# Bank0_I_O.net
KiCad netlist of a schematic drawn in Altium Designer
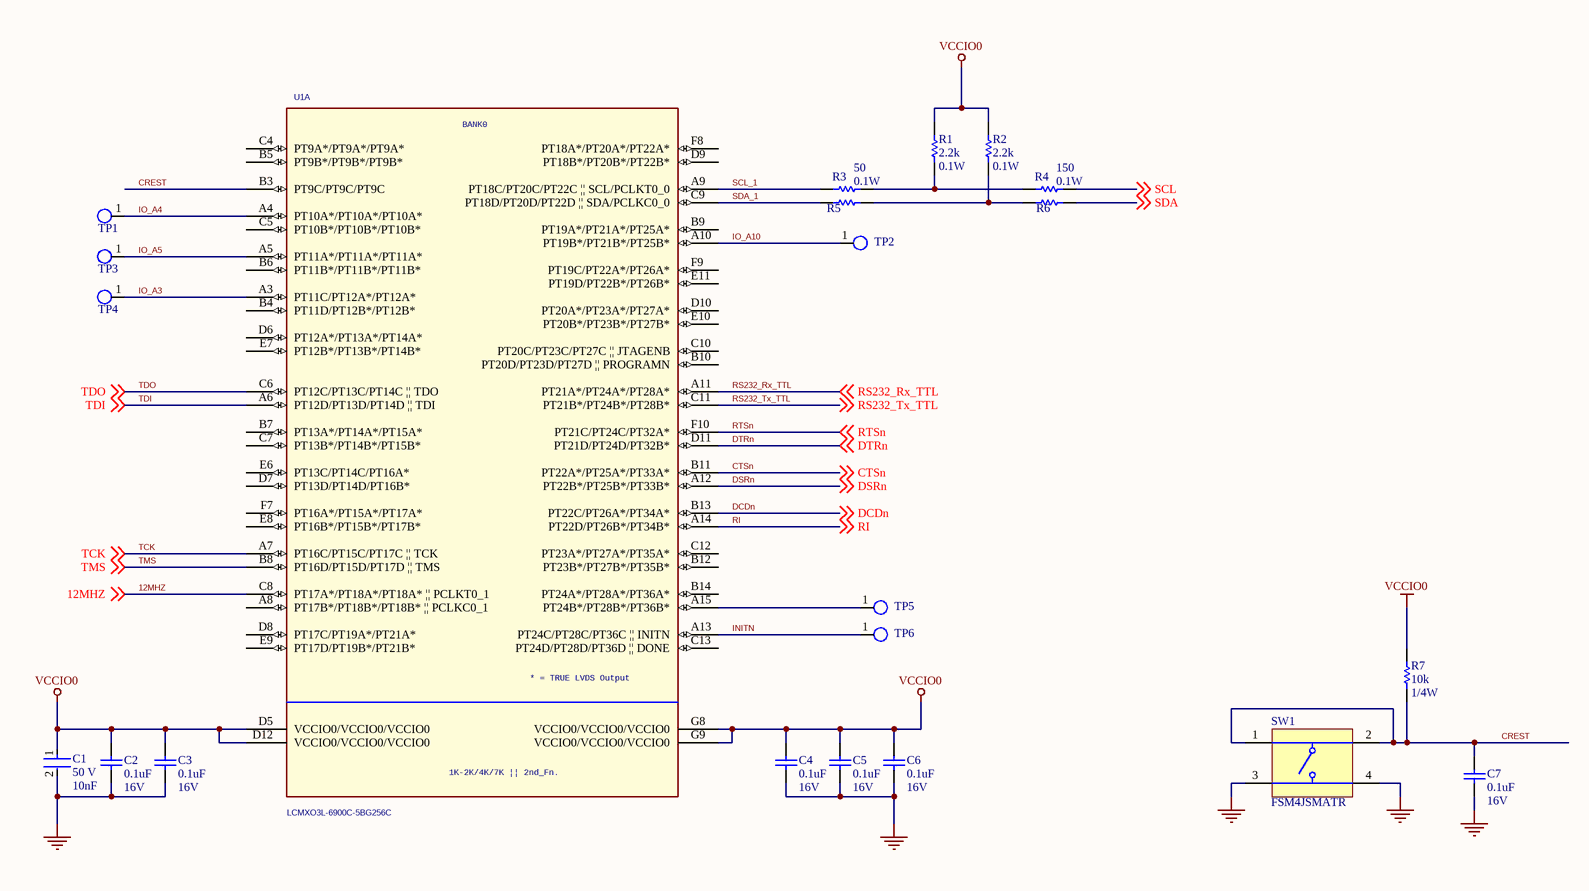
[diagram p0: Bank0_I_O.SchDoc]

(export (version "E")
  (design (tool "Eeschema 10.0.6"))
  (components
    (comp (ref "C1")
      (value "10nF")
      (footprint "FP-C0805C-DN-MFG")
      (description "CAP CER 10000PF 50V X7R 0805")
      (fields
        (field (name "VOLTAGE") "50 V")
        (field (name "PART NUMBER") "C0805C103K5RACAUTO")
        (field (name "MANUFACTURER") "KEMET")
      )
      (libsource (lib "Altium Content Vault") (part "b4654b650e69147ec39a6b967a45e02"))
    )
    (comp (ref "C2")
      (value "0.1uF")
      (footprint "CAPC1608X87X35ML15T15")
      (description "Ceramic Capacitor 0.1uF 16V +-10% X7R0603")
      (fields
        (field (name "PART NUMBER") "C0603C104M4RACTU")
        (field (name "MANUFACTURER") "Kemet")
        (field (name "VOLTAGE") "16V")
      )
      (libsource (lib "Altium Content Vault") (part "CAP"))
    )
    (comp (ref "C3")
      (value "0.1uF")
      (footprint "CAPC1608X87X35ML15T15")
      (description "Ceramic Capacitor 0.1uF 16V +-10% X7R0603")
      (fields
        (field (name "PART NUMBER") "C0603C104M4RACTU")
        (field (name "MANUFACTURER") "Kemet")
        (field (name "VOLTAGE") "16V")
      )
      (libsource (lib "Altium Content Vault") (part "CAP"))
    )
    (comp (ref "C4")
      (value "0.1uF")
      (footprint "CAPC1608X87X35ML15T15")
      (description "Ceramic Capacitor 0.1uF 16V +-10% X7R0603")
      (fields
        (field (name "PART NUMBER") "C0603C104M4RACTU")
        (field (name "MANUFACTURER") "Kemet")
        (field (name "VOLTAGE") "16V")
      )
      (libsource (lib "Altium Content Vault") (part "CAP"))
    )
    (comp (ref "C5")
      (value "0.1uF")
      (footprint "CAPC1608X87X35ML15T15")
      (description "Ceramic Capacitor 0.1uF 16V +-10% X7R0603")
      (fields
        (field (name "PART NUMBER") "C0603C104M4RACTU")
        (field (name "MANUFACTURER") "Kemet")
        (field (name "VOLTAGE") "16V")
      )
      (libsource (lib "Altium Content Vault") (part "CAP"))
    )
    (comp (ref "C6")
      (value "0.1uF")
      (footprint "CAPC1608X87X35ML15T15")
      (description "Ceramic Capacitor 0.1uF 16V +-10% X7R0603")
      (fields
        (field (name "PART NUMBER") "C0603C104M4RACTU")
        (field (name "MANUFACTURER") "Kemet")
        (field (name "VOLTAGE") "16V")
      )
      (libsource (lib "Altium Content Vault") (part "CAP"))
    )
    (comp (ref "C7")
      (value "0.1uF")
      (footprint "CAPC1608X87X35ML15T15")
      (description "Ceramic Capacitor 0.1uF 16V +-10% X7R0603")
      (fields
        (field (name "PART NUMBER") "C0603C104M4RACTU")
        (field (name "MANUFACTURER") "Kemet")
        (field (name "VOLTAGE") "16V")
      )
      (libsource (lib "Altium Content Vault") (part "CAP"))
    )
    (comp (ref "R1")
      (value "2.2k")
      (footprint "RESC1608X55X25LL10T15")
      (fields
        (field (name "TOLERANCE") "1%")
        (field (name "VOLTAGE") "50V")
        (field (name "MANUFACTURER") "Yageo")
        (field (name "POWER") "0.1W")
      )
      (libsource (lib "Altium Content Vault") (part "RES-2"))
    )
    (comp (ref "R2")
      (value "2.2k")
      (footprint "RESC1608X55X25LL10T15")
      (fields
        (field (name "TOLERANCE") "1%")
        (field (name "VOLTAGE") "50V")
        (field (name "MANUFACTURER") "Yageo")
        (field (name "POWER") "0.1W")
      )
      (libsource (lib "Altium Content Vault") (part "RES-2"))
    )
    (comp (ref "R3")
      (value "50")
      (footprint "RESC1609X50X30NL10T20")
      (fields
        (field (name "PART NUMBER") "CRCW060350R0FKEA")
        (field (name "MANUFACTURER") "Vishay Dale")
        (field (name "POWER") "0.1W")
      )
      (libsource (lib "Altium Content Vault") (part "RES"))
    )
    (comp (ref "R4")
      (value "150")
      (footprint "RESC1608X55X30NL15T15")
      (fields
        (field (name "PART NUMBER") "ERJ-3EKF1500V")
        (field (name "MANUFACTURER") "Panasonic")
        (field (name "POWER") "0.1W")
      )
      (libsource (lib "Altium Content Vault") (part "RES"))
    )
    (comp (ref "R5")
      (value "CRCW060350R0FKEA")
      (footprint "RESC1609X50X30NL10T20")
      (fields (field (name "MANUFACTURER") "Vishay Dale") (field (name "POWER") "0.1W"))
      (libsource (lib "Altium Content Vault") (part "RES"))
    )
    (comp (ref "R6")
      (value "ERJ-3EKF1500V")
      (footprint "RESC1608X55X30NL15T15")
      (fields (field (name "MANUFACTURER") "Panasonic") (field (name "POWER") "0.1W"))
      (libsource (lib "Altium Content Vault") (part "RES"))
    )
    (comp (ref "R7")
      (value "10k")
      (footprint "RESC3216X70X50NL05T20")
      (description "Res Thick Film 1206 10k Ohms 5% 1/4W")
      (fields
        (field (name "PART NUMBER") "ERJ-8GEYJ103V")
        (field (name "MANUFACTURER") "Panasonic")
        (field (name "POWER") "1/4W")
      )
      (libsource (lib "Altium Content Vault") (part "RES"))
    )
    (comp (ref "SW1")
      (value "FSM4JSMATR")
      (footprint "TECO-FSM4JSMATR_V")
      (description "Micro Miniature Push Button Switch FSM JSM, 50 mA, -35 to 85 degC, 4-Pin SMD, RoHS, Tape and Reel")
      (fields (field (name "MANUFACTURER") "TE Connectivity"))
      (libsource (lib "Altium Content Vault") (part "SW-SPST-4_A"))
    )
    (comp (ref "TP1")
      (value "Test_Point_SMD")
      (footprint "Test_Point_SMD")
      (libsource (lib "Edson") (part "Test_Point_SMD"))
    )
    (comp (ref "TP2")
      (value "Test_Point_SMD")
      (footprint "Test_Point_SMD")
      (libsource (lib "Edson") (part "Test_Point_SMD"))
    )
    (comp (ref "TP3")
      (value "Test_Point_SMD")
      (footprint "Test_Point_SMD")
      (libsource (lib "Edson") (part "Test_Point_SMD"))
    )
    (comp (ref "TP4")
      (value "Test_Point_SMD")
      (footprint "Test_Point_SMD")
      (libsource (lib "Edson") (part "Test_Point_SMD"))
    )
    (comp (ref "TP5")
      (value "Test_Point_SMD")
      (footprint "Test_Point_SMD")
      (libsource (lib "Edson") (part "Test_Point_SMD"))
    )
    (comp (ref "TP6")
      (value "Test_Point_SMD")
      (footprint "Test_Point_SMD")
      (libsource (lib "Edson") (part "Test_Point_SMD"))
    )
    (comp (ref "U1")
      (value "LCMXO3L-6900C-5BG256C")
      (footprint "BGA256C80P16X16_1400X1400X170")
      (description "IC FPGA 6864LUTS 256BGA")
      (fields (field (name "MANUFACTURER") "Lattice semi"))
      (libsource (lib "*") (part "LCMXO3L-1K/2K/4K/7K-BG256"))
    )
  )
  (nets
    (net (code "1") (name "/CREST") (class "Default")
      (node (ref "C7") (pin "1") (pinfunction "1_1") (pintype "passive"))
      (node (ref "R7") (pin "2") (pinfunction "2_2") (pintype "passive"))
      (node (ref "SW1") (pin "1") (pinfunction "1_1") (pintype "passive"))
      (node (ref "SW1") (pin "2") (pinfunction "2_2") (pintype "passive"))
      (node (ref "U1") (pin "B3") (pinfunction "PT9C/PT9C/PT9C_B3") (pintype "bidirectional"))
    )
    (net (code "2") (name "/INITN") (class "Default")
      (node (ref "TP6") (pin "1") (pinfunction "TP_1") (pintype "passive"))
      (node (ref "U1") (pin "A13") (pinfunction "PT24C/PT28C/PT36C_Ζ_INITN_A13") (pintype "bidirectional"))
    )
    (net (code "3") (name "/IO_A3") (class "Default")
      (node (ref "TP4") (pin "1") (pinfunction "TP_1") (pintype "passive"))
      (node (ref "U1") (pin "A3") (pinfunction "PT11C/PT12A*/PT12A*_A3") (pintype "bidirectional"))
    )
    (net (code "4") (name "/IO_A4") (class "Default")
      (node (ref "TP1") (pin "1") (pinfunction "TP_1") (pintype "passive"))
      (node (ref "U1") (pin "A4") (pinfunction "PT10A*/PT10A*/PT10A*_A4") (pintype "bidirectional"))
    )
    (net (code "5") (name "/IO_A5") (class "Default")
      (node (ref "TP3") (pin "1") (pinfunction "TP_1") (pintype "passive"))
      (node (ref "U1") (pin "A5") (pinfunction "PT11A*/PT11A*/PT11A*_A5") (pintype "bidirectional"))
    )
    (net (code "6") (name "/IO_A10") (class "Default")
      (node (ref "TP2") (pin "1") (pinfunction "TP_1") (pintype "passive"))
      (node (ref "U1") (pin "A10") (pinfunction "PT19B*/PT21B*/PT25B*_A10") (pintype "bidirectional"))
    )
    (net (code "7") (name "/SCL_1") (class "Default")
      (node (ref "R3") (pin "1") (pinfunction "1_1") (pintype "passive"))
      (node (ref "U1") (pin "A9") (pinfunction "PT18C/PT20C/PT22C_Ζ_SCL/PCLKT0_0_A9") (pintype "bidirectional"))
    )
    (net (code "8") (name "/SDA_1") (class "Default")
      (node (ref "R5") (pin "1") (pinfunction "1_1") (pintype "passive"))
      (node (ref "U1") (pin "C9") (pinfunction "PT18D/PT20D/PT22D_Ζ_SDA/PCLKC0_0_C9") (pintype "bidirectional"))
    )
    (net (code "9") (name "12MHZ") (class "Default")
      (node (ref "U1") (pin "C8") (pinfunction "PT17A*/PT18A*/PT18A*_Ζ_PCLKT0_1_C8") (pintype "bidirectional"))
    )
    (net (code "10") (name "CTSn") (class "Default")
      (node (ref "U1") (pin "B11") (pinfunction "PT22A*/PT25A*/PT33A*_B11") (pintype "bidirectional"))
    )
    (net (code "11") (name "DCDn") (class "Default")
      (node (ref "U1") (pin "B13") (pinfunction "PT22C/PT26A*/PT34A*_B13") (pintype "bidirectional"))
    )
    (net (code "12") (name "DSRn") (class "Default")
      (node (ref "U1") (pin "A12") (pinfunction "PT22B*/PT25B*/PT33B*_A12") (pintype "bidirectional"))
    )
    (net (code "13") (name "DTRn") (class "Default")
      (node (ref "U1") (pin "D11") (pinfunction "PT21D/PT24D/PT32B*_D11") (pintype "bidirectional"))
    )
    (net (code "14") (name "GND") (class "Default")
      (node (ref "C1") (pin "2") (pinfunction "2_2") (pintype "passive"))
      (node (ref "C2") (pin "2") (pinfunction "2_2") (pintype "passive"))
      (node (ref "C3") (pin "2") (pinfunction "2_2") (pintype "passive"))
      (node (ref "C4") (pin "2") (pinfunction "2_2") (pintype "passive"))
      (node (ref "C5") (pin "2") (pinfunction "2_2") (pintype "passive"))
      (node (ref "C6") (pin "2") (pinfunction "2_2") (pintype "passive"))
      (node (ref "C7") (pin "2") (pinfunction "2_2") (pintype "passive"))
      (node (ref "SW1") (pin "3") (pinfunction "3_3") (pintype "passive"))
      (node (ref "SW1") (pin "4") (pinfunction "4_4") (pintype "passive"))
    )
    (net (code "15") (name "Net-(R1-Pad1)") (class "Default")
      (node (ref "R1") (pin "1") (pinfunction "1_1") (pintype "passive"))
      (node (ref "R3") (pin "2") (pinfunction "2_2") (pintype "passive"))
      (node (ref "R4") (pin "1") (pinfunction "1_1") (pintype "passive"))
    )
    (net (code "16") (name "Net-(R2-Pad1)") (class "Default")
      (node (ref "R2") (pin "1") (pinfunction "1_1") (pintype "passive"))
      (node (ref "R5") (pin "2") (pinfunction "2_2") (pintype "passive"))
      (node (ref "R6") (pin "1") (pinfunction "1_1") (pintype "passive"))
    )
    (net (code "17") (name "Net-(TP5-TP)") (class "Default")
      (node (ref "TP5") (pin "1") (pinfunction "TP_1") (pintype "passive"))
      (node (ref "U1") (pin "A15") (pinfunction "PT24B*/PT28B*/PT36B*_A15") (pintype "bidirectional"))
    )
    (net (code "18") (name "RI") (class "Default")
      (node (ref "U1") (pin "A14") (pinfunction "PT22D/PT26B*/PT34B*_A14") (pintype "bidirectional"))
    )
    (net (code "19") (name "RS232_Rx_TTL") (class "Default")
      (node (ref "U1") (pin "A11") (pinfunction "PT21A*/PT24A*/PT28A*_A11") (pintype "bidirectional"))
    )
    (net (code "20") (name "RS232_Tx_TTL") (class "Default")
      (node (ref "U1") (pin "C11") (pinfunction "PT21B*/PT24B*/PT28B*_C11") (pintype "bidirectional"))
    )
    (net (code "21") (name "RTSn") (class "Default")
      (node (ref "U1") (pin "F10") (pinfunction "PT21C/PT24C/PT32A*_F10") (pintype "bidirectional"))
    )
    (net (code "22") (name "SCL") (class "Default")
      (node (ref "R4") (pin "2") (pinfunction "2_2") (pintype "passive"))
    )
    (net (code "23") (name "SDA") (class "Default")
      (node (ref "R6") (pin "2") (pinfunction "2_2") (pintype "passive"))
    )
    (net (code "24") (name "TCK") (class "Default")
      (node (ref "U1") (pin "A7") (pinfunction "PT16C/PT15C/PT17C_Ζ_TCK_A7") (pintype "bidirectional"))
    )
    (net (code "25") (name "TDI") (class "Default")
      (node (ref "U1") (pin "A6") (pinfunction "PT12D/PT13D/PT14D_Ζ_TDI_A6") (pintype "bidirectional"))
    )
    (net (code "26") (name "TDO") (class "Default")
      (node (ref "U1") (pin "C6") (pinfunction "PT12C/PT13C/PT14C_Ζ_TDO_C6") (pintype "bidirectional"))
    )
    (net (code "27") (name "TMS") (class "Default")
      (node (ref "U1") (pin "B8") (pinfunction "PT16D/PT15D/PT17D_Ζ_TMS_B8") (pintype "bidirectional"))
    )
    (net (code "28") (name "VCCIO0") (class "Default")
      (node (ref "C1") (pin "1") (pinfunction "1_1") (pintype "passive"))
      (node (ref "C2") (pin "1") (pinfunction "1_1") (pintype "passive"))
      (node (ref "C3") (pin "1") (pinfunction "1_1") (pintype "passive"))
      (node (ref "C4") (pin "1") (pinfunction "1_1") (pintype "passive"))
      (node (ref "C5") (pin "1") (pinfunction "1_1") (pintype "passive"))
      (node (ref "C6") (pin "1") (pinfunction "1_1") (pintype "passive"))
      (node (ref "R1") (pin "2") (pinfunction "2_2") (pintype "passive"))
      (node (ref "R2") (pin "2") (pinfunction "2_2") (pintype "passive"))
      (node (ref "R7") (pin "1") (pinfunction "1_1") (pintype "passive"))
      (node (ref "U1") (pin "D12") (pinfunction "VCCIO0/VCCIO0/VCCIO0_D12") (pintype "power_in"))
      (node (ref "U1") (pin "D5") (pinfunction "VCCIO0/VCCIO0/VCCIO0_D5") (pintype "power_in"))
      (node (ref "U1") (pin "G8") (pinfunction "VCCIO0/VCCIO0/VCCIO0_G8") (pintype "power_in"))
      (node (ref "U1") (pin "G9") (pinfunction "VCCIO0/VCCIO0/VCCIO0_G9") (pintype "power_in"))
    )
    (net (code "29") (name "unconnected-(U1A-PT9A*{slash}PT9A*{slash}PT9A*-PadC4)") (class "Default")
      (node (ref "U1") (pin "C4") (pinfunction "PT9A*/PT9A*/PT9A*_C4") (pintype "bidirectional"))
    )
    (net (code "30") (name "unconnected-(U1A-PT9B*{slash}PT9B*{slash}PT9B*-PadB5)") (class "Default")
      (node (ref "U1") (pin "B5") (pinfunction "PT9B*/PT9B*/PT9B*_B5") (pintype "bidirectional"))
    )
    (net (code "31") (name "unconnected-(U1A-PT10B*{slash}PT10B*{slash}PT10B*-PadC5)") (class "Default")
      (node (ref "U1") (pin "C5") (pinfunction "PT10B*/PT10B*/PT10B*_C5") (pintype "bidirectional"))
    )
    (net (code "32") (name "unconnected-(U1A-PT11B*{slash}PT11B*{slash}PT11B*-PadB6)") (class "Default")
      (node (ref "U1") (pin "B6") (pinfunction "PT11B*/PT11B*/PT11B*_B6") (pintype "bidirectional"))
    )
    (net (code "33") (name "unconnected-(U1A-PT11D{slash}PT12B*{slash}PT12B*-PadB4)") (class "Default")
      (node (ref "U1") (pin "B4") (pinfunction "PT11D/PT12B*/PT12B*_B4") (pintype "bidirectional"))
    )
    (net (code "34") (name "unconnected-(U1A-PT12A*{slash}PT13A*{slash}PT14A*-PadD6)") (class "Default")
      (node (ref "U1") (pin "D6") (pinfunction "PT12A*/PT13A*/PT14A*_D6") (pintype "bidirectional"))
    )
    (net (code "35") (name "unconnected-(U1A-PT12B*{slash}PT13B*{slash}PT14B*-PadE7)") (class "Default")
      (node (ref "U1") (pin "E7") (pinfunction "PT12B*/PT13B*/PT14B*_E7") (pintype "bidirectional"))
    )
    (net (code "36") (name "unconnected-(U1A-PT13A*{slash}PT14A*{slash}PT15A*-PadB7)") (class "Default")
      (node (ref "U1") (pin "B7") (pinfunction "PT13A*/PT14A*/PT15A*_B7") (pintype "bidirectional"))
    )
    (net (code "37") (name "unconnected-(U1A-PT13B*{slash}PT14B*{slash}PT15B*-PadC7)") (class "Default")
      (node (ref "U1") (pin "C7") (pinfunction "PT13B*/PT14B*/PT15B*_C7") (pintype "bidirectional"))
    )
    (net (code "38") (name "unconnected-(U1A-PT13C{slash}PT14C{slash}PT16A*-PadE6)") (class "Default")
      (node (ref "U1") (pin "E6") (pinfunction "PT13C/PT14C/PT16A*_E6") (pintype "bidirectional"))
    )
    (net (code "39") (name "unconnected-(U1A-PT13D{slash}PT14D{slash}PT16B*-PadD7)") (class "Default")
      (node (ref "U1") (pin "D7") (pinfunction "PT13D/PT14D/PT16B*_D7") (pintype "bidirectional"))
    )
    (net (code "40") (name "unconnected-(U1A-PT16A*{slash}PT15A*{slash}PT17A*-PadF7)") (class "Default")
      (node (ref "U1") (pin "F7") (pinfunction "PT16A*/PT15A*/PT17A*_F7") (pintype "bidirectional"))
    )
    (net (code "41") (name "unconnected-(U1A-PT16B*{slash}PT15B*{slash}PT17B*-PadE8)") (class "Default")
      (node (ref "U1") (pin "E8") (pinfunction "PT16B*/PT15B*/PT17B*_E8") (pintype "bidirectional"))
    )
    (net (code "42") (name "unconnected-(U1A-PT17B*{slash}PT18B*{slash}PT18B*_Ζ_PCLKC0_1-PadA8)") (class "Default")
      (node (ref "U1") (pin "A8") (pinfunction "PT17B*/PT18B*/PT18B*_Ζ_PCLKC0_1_A8") (pintype "bidirectional"))
    )
    (net (code "43") (name "unconnected-(U1A-PT17C{slash}PT19A*{slash}PT21A*-PadD8)") (class "Default")
      (node (ref "U1") (pin "D8") (pinfunction "PT17C/PT19A*/PT21A*_D8") (pintype "bidirectional"))
    )
    (net (code "44") (name "unconnected-(U1A-PT17D{slash}PT19B*{slash}PT21B*-PadE9)") (class "Default")
      (node (ref "U1") (pin "E9") (pinfunction "PT17D/PT19B*/PT21B*_E9") (pintype "bidirectional"))
    )
    (net (code "45") (name "unconnected-(U1A-PT18A*{slash}PT20A*{slash}PT22A*-PadF8)") (class "Default")
      (node (ref "U1") (pin "F8") (pinfunction "PT18A*/PT20A*/PT22A*_F8") (pintype "bidirectional"))
    )
    (net (code "46") (name "unconnected-(U1A-PT18B*{slash}PT20B*{slash}PT22B*-PadD9)") (class "Default")
      (node (ref "U1") (pin "D9") (pinfunction "PT18B*/PT20B*/PT22B*_D9") (pintype "bidirectional"))
    )
    (net (code "47") (name "unconnected-(U1A-PT19A*{slash}PT21A*{slash}PT25A*-PadB9)") (class "Default")
      (node (ref "U1") (pin "B9") (pinfunction "PT19A*/PT21A*/PT25A*_B9") (pintype "bidirectional"))
    )
    (net (code "48") (name "unconnected-(U1A-PT19C{slash}PT22A*{slash}PT26A*-PadF9)") (class "Default")
      (node (ref "U1") (pin "F9") (pinfunction "PT19C/PT22A*/PT26A*_F9") (pintype "bidirectional"))
    )
    (net (code "49") (name "unconnected-(U1A-PT19D{slash}PT22B*{slash}PT26B*-PadE11)") (class "Default")
      (node (ref "U1") (pin "E11") (pinfunction "PT19D/PT22B*/PT26B*_E11") (pintype "bidirectional"))
    )
    (net (code "50") (name "unconnected-(U1A-PT20A*{slash}PT23A*{slash}PT27A*-PadD10)") (class "Default")
      (node (ref "U1") (pin "D10") (pinfunction "PT20A*/PT23A*/PT27A*_D10") (pintype "bidirectional"))
    )
    (net (code "51") (name "unconnected-(U1A-PT20B*{slash}PT23B*{slash}PT27B*-PadE10)") (class "Default")
      (node (ref "U1") (pin "E10") (pinfunction "PT20B*/PT23B*/PT27B*_E10") (pintype "bidirectional"))
    )
    (net (code "52") (name "unconnected-(U1A-PT20C{slash}PT23C{slash}PT27C_Ζ_JTAGENB-PadC10)") (class "Default")
      (node (ref "U1") (pin "C10") (pinfunction "PT20C/PT23C/PT27C_Ζ_JTAGENB_C10") (pintype "bidirectional"))
    )
    (net (code "53") (name "unconnected-(U1A-PT20D{slash}PT23D{slash}PT27D_Ζ_PROGRAMN-PadB10)") (class "Default")
      (node (ref "U1") (pin "B10") (pinfunction "PT20D/PT23D/PT27D_Ζ_PROGRAMN_B10") (pintype "bidirectional"))
    )
    (net (code "54") (name "unconnected-(U1A-PT23A*{slash}PT27A*{slash}PT35A*-PadC12)") (class "Default")
      (node (ref "U1") (pin "C12") (pinfunction "PT23A*/PT27A*/PT35A*_C12") (pintype "bidirectional"))
    )
    (net (code "55") (name "unconnected-(U1A-PT23B*{slash}PT27B*{slash}PT35B*-PadB12)") (class "Default")
      (node (ref "U1") (pin "B12") (pinfunction "PT23B*/PT27B*/PT35B*_B12") (pintype "bidirectional"))
    )
    (net (code "56") (name "unconnected-(U1A-PT24A*{slash}PT28A*{slash}PT36A*-PadB14)") (class "Default")
      (node (ref "U1") (pin "B14") (pinfunction "PT24A*/PT28A*/PT36A*_B14") (pintype "bidirectional"))
    )
    (net (code "57") (name "unconnected-(U1A-PT24D{slash}PT28D{slash}PT36D_Ζ_DONE-PadC13)") (class "Default")
      (node (ref "U1") (pin "C13") (pinfunction "PT24D/PT28D/PT36D_Ζ_DONE_C13") (pintype "bidirectional"))
    )
  )
)
